# ProPrj_ADC__2025-07-17.net
KiCad netlist of a schematic drawn in EasyEDA Pro
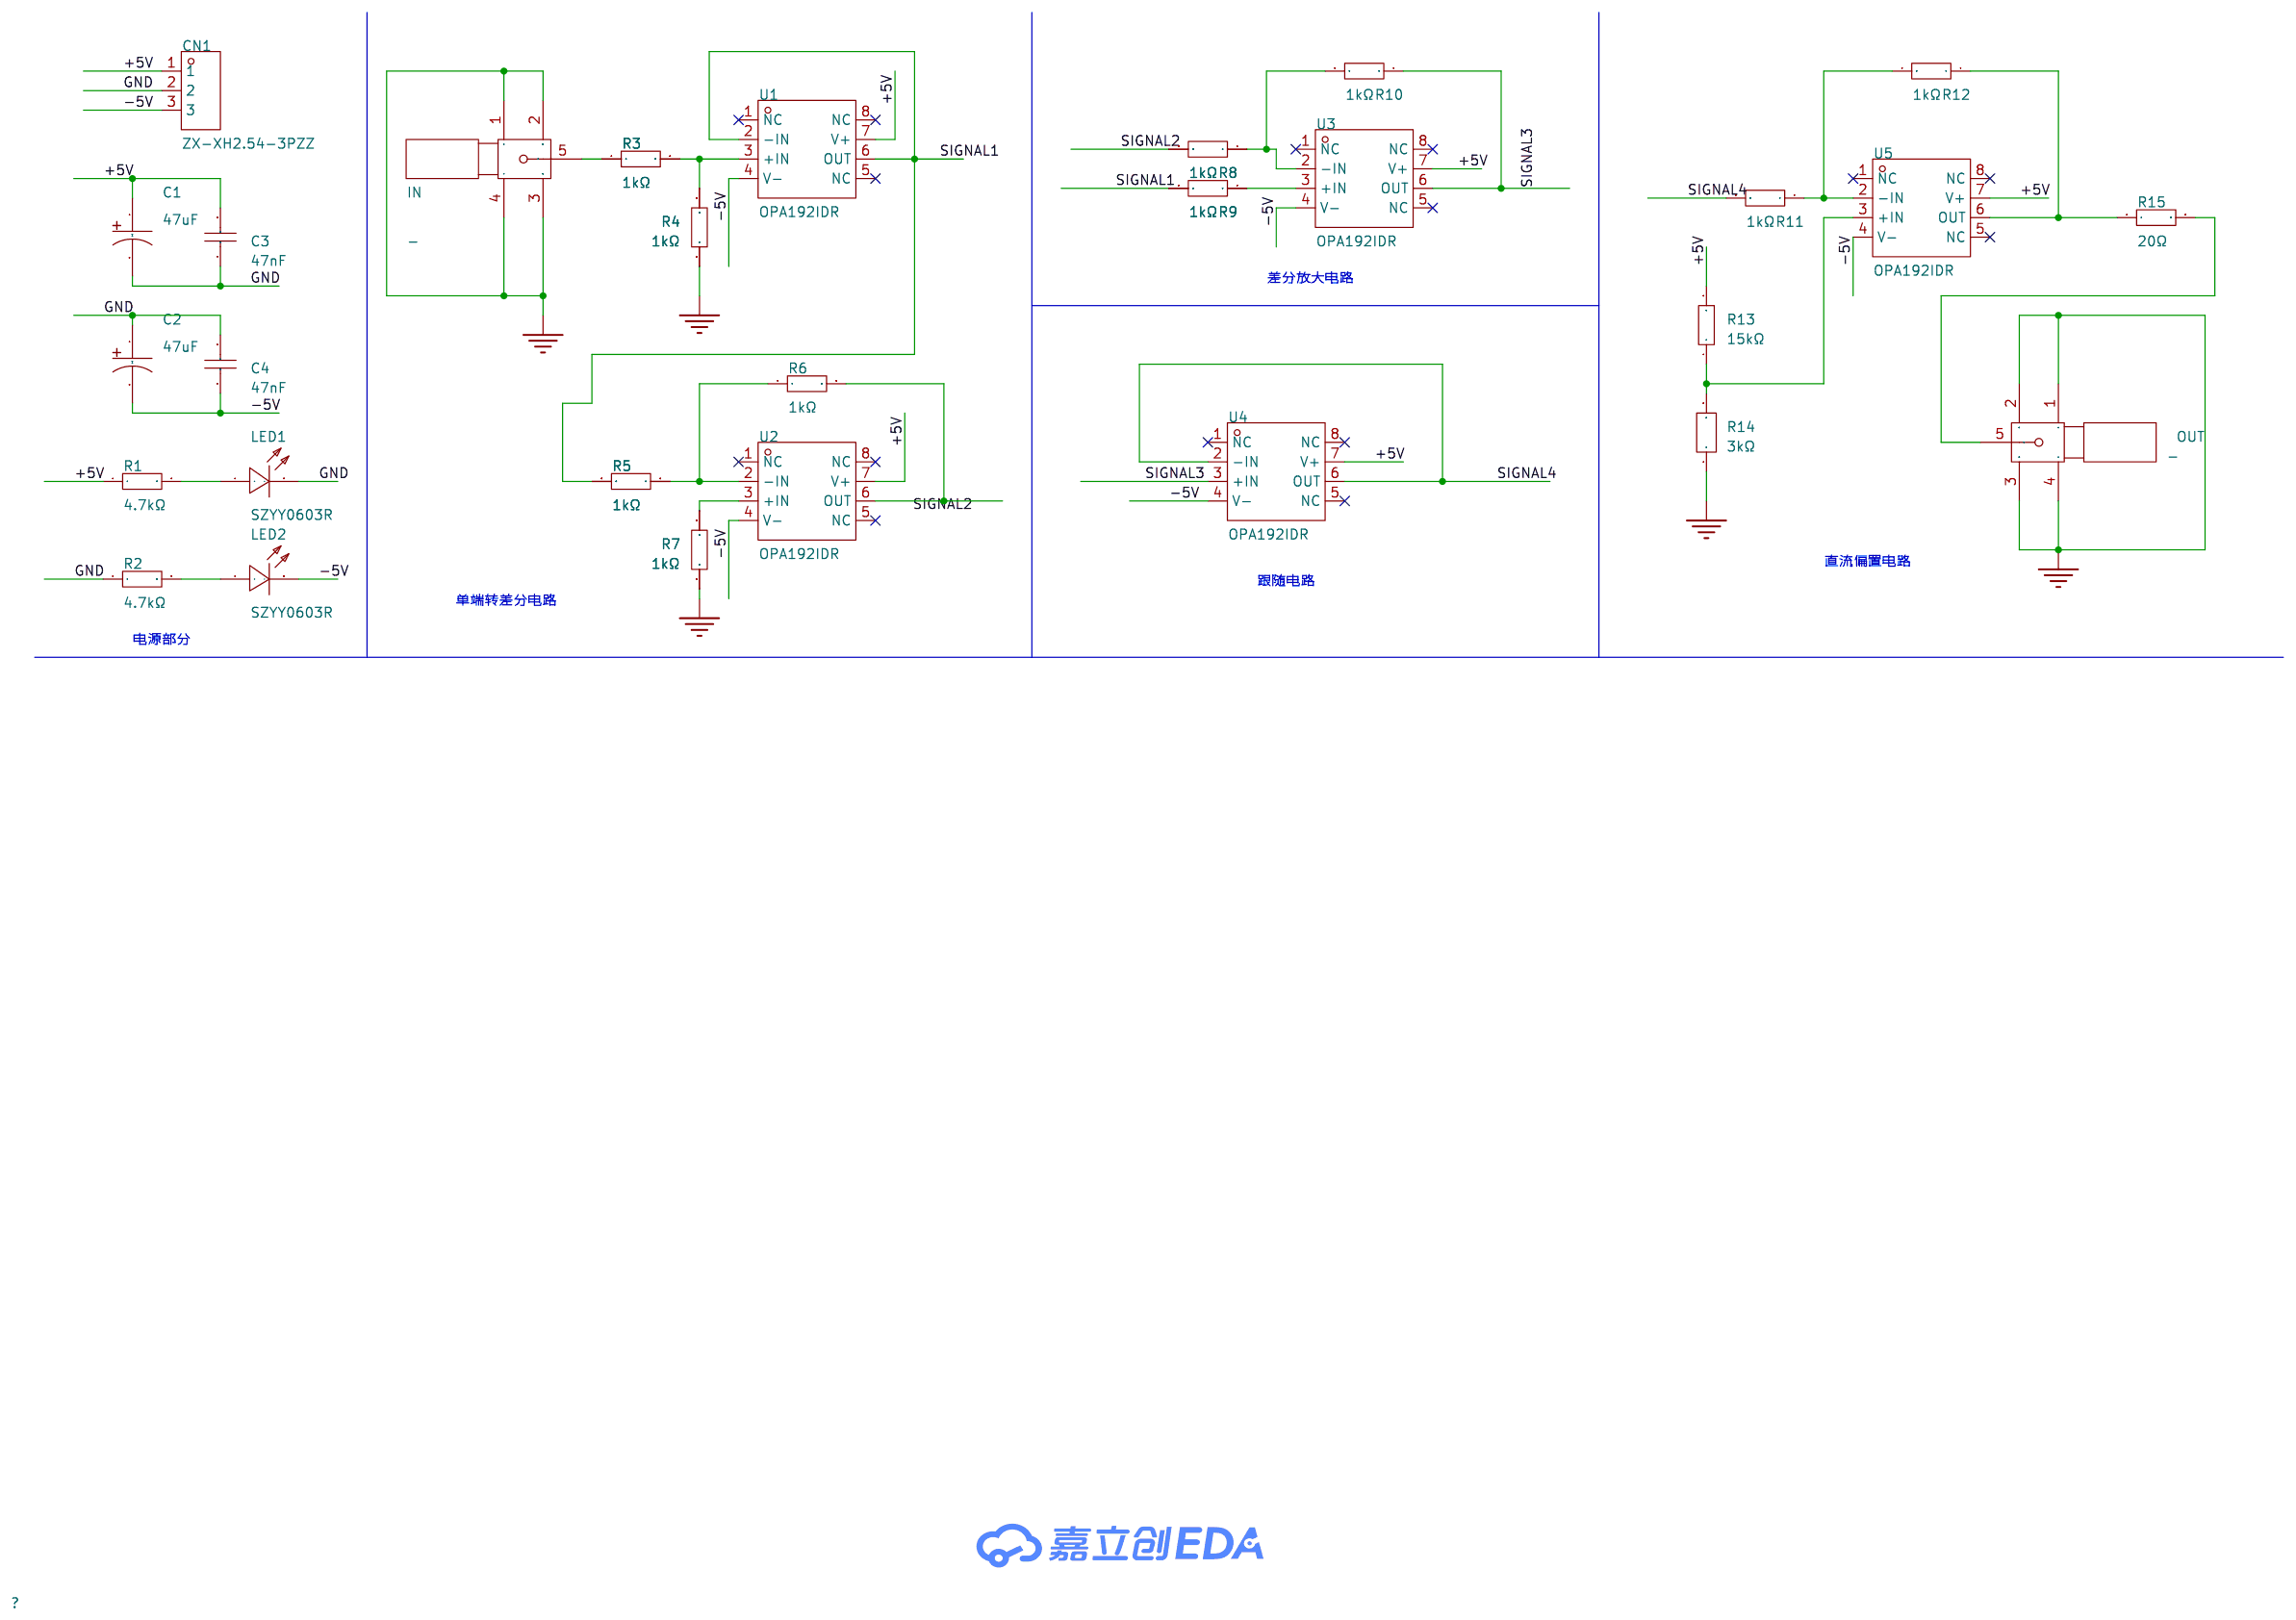
[diagram p0: schematic sheet]

(export (version "E")
  (design (tool "Eeschema 10.0.6"))
  (components
    (comp (ref "C1")
      (value "47uF")
      (footprint "easyedapro:CAP-TH_BD5.0-P2.00-D0.8-FD")
      (description "容值:47uF;精度:±20%;额定电压:25V;纹波电流:250mA@100kHz;等效串联电阻(ESR):300mΩ@100kHz;")
      (fields
        (field (name "Manufacturer Part") "NXB25V47M5*11 2.5TP")
        (field (name "Manufacturer") "SAMYOUNG(韩国三莹)")
      )
      (libsource (lib "easyedapro") (part "NXB25VB47M5*11_2.5TP"))
    )
    (comp (ref "C2")
      (value "47uF")
      (footprint "easyedapro:CAP-TH_BD5.0-P2.00-D0.8-FD")
      (description "容值:47uF;精度:±20%;额定电压:25V;纹波电流:250mA@100kHz;等效串联电阻(ESR):300mΩ@100kHz;")
      (fields
        (field (name "Manufacturer Part") "NXB25V47M5*11 2.5TP")
        (field (name "Manufacturer") "SAMYOUNG(韩国三莹)")
      )
      (libsource (lib "easyedapro") (part "NXB25VB47M5*11_2.5TP"))
    )
    (comp (ref "C3")
      (value "47nF")
      (footprint "easyedapro:C0805")
      (description "容值:47nF;精度:±10%;额定电压:50V;材质(温度系数):X7R;")
      (fields
        (field (name "Manufacturer Part") "CL21B473KBCNNNC")
        (field (name "Manufacturer") "SAMSUNG(三星)")
      )
      (libsource (lib "easyedapro") (part "CL21B473KBCNNNC"))
    )
    (comp (ref "C4")
      (value "47nF")
      (footprint "easyedapro:C0805")
      (description "容值:47nF;精度:±10%;额定电压:50V;材质(温度系数):X7R;")
      (fields
        (field (name "Manufacturer Part") "CL21B473KBCNNNC")
        (field (name "Manufacturer") "SAMSUNG(三星)")
      )
      (libsource (lib "easyedapro") (part "CL21B473KBCNNNC"))
    )
    (comp (ref "CN1")
      (value "ZX-XH2.54-3PZZ")
      (footprint "easyedapro:CONN-TH_3P-P2.54_2501S-3P")
      (fields (field (name "Manufacturer") "Megastar(兆星)"))
      (libsource (lib "easyedapro") (part "ZX-XH2.54-3PZZ"))
    )
    (comp (ref "IN")
      (value "-")
      (footprint "easyedapro:SMA-SMD_BWSMA-KE-P001")
      (description "连接器类型:板端;接口类型:内孔;端口数量:1;接口直径:5.2mm;接口长度/高度:-;频率:-;射频系列:SMA;阻抗:50Ω;样式:偏脚;工作温度:-;")
      (fields
        (field (name "Manufacturer Part") "BWSMA-KE-P001")
        (field (name "Manufacturer") "BAT WIRELESS(蝙蝠无线)")
      )
      (libsource (lib "easyedapro") (part "BWSMA-KE-P001"))
    )
    (comp (ref "LED1")
      (value "SZYY0603R")
      (footprint "easyedapro:LED0603-R-RD")
      (fields (field (name "Manufacturer") "yongyu(永裕光电)"))
      (libsource (lib "easyedapro") (part "SZYY0603R"))
    )
    (comp (ref "LED2")
      (value "SZYY0603R")
      (footprint "easyedapro:LED0603-R-RD")
      (fields (field (name "Manufacturer") "yongyu(永裕光电)"))
      (libsource (lib "easyedapro") (part "SZYY0603R"))
    )
    (comp (ref "OUT")
      (value "-")
      (footprint "easyedapro:SMA-SMD_BWSMA-KE-P001")
      (description "连接器类型:板端;接口类型:内孔;端口数量:1;接口直径:5.2mm;接口长度/高度:-;频率:-;射频系列:SMA;阻抗:50Ω;样式:偏脚;工作温度:-;")
      (fields
        (field (name "Manufacturer Part") "BWSMA-KE-P001")
        (field (name "Manufacturer") "BAT WIRELESS(蝙蝠无线)")
      )
      (libsource (lib "easyedapro") (part "BWSMA-KE-P001"))
    )
    (comp (ref "R1")
      (value "4.7kΩ")
      (footprint "easyedapro:R0805")
      (description "电阻类型:厚膜电阻;阻值:4.7kΩ;精度:±1%;功率:125mW;最大工作电压:150V;温度系数:±100ppm/°C;")
      (fields
        (field (name "Manufacturer Part") "0805W8F4701T5E")
        (field (name "Manufacturer") "UNI-ROYAL(厚声)")
      )
      (libsource (lib "easyedapro") (part "0805W8F4701T5E"))
    )
    (comp (ref "R2")
      (value "4.7kΩ")
      (footprint "easyedapro:R0805")
      (description "电阻类型:厚膜电阻;阻值:4.7kΩ;精度:±1%;功率:125mW;最大工作电压:150V;温度系数:±100ppm/°C;")
      (fields
        (field (name "Manufacturer Part") "0805W8F4701T5E")
        (field (name "Manufacturer") "UNI-ROYAL(厚声)")
      )
      (libsource (lib "easyedapro") (part "0805W8F4701T5E"))
    )
    (comp (ref "R3")
      (value "1kΩ")
      (footprint "easyedapro:R0805")
      (description "电阻类型:厚膜电阻;阻值:1kΩ;精度:±1%;功率:125mW;最大工作电压:150V;温度系数:±100ppm/°C;")
      (fields
        (field (name "Manufacturer Part") "0805W8F1001T5E")
        (field (name "Manufacturer") "UNI-ROYAL(厚声)")
      )
      (libsource (lib "easyedapro") (part "0805W8F1001T5E"))
    )
    (comp (ref "R4")
      (value "1kΩ")
      (footprint "easyedapro:R0805")
      (description "电阻类型:厚膜电阻;阻值:1kΩ;精度:±1%;功率:125mW;最大工作电压:150V;温度系数:±100ppm/°C;")
      (fields
        (field (name "Manufacturer Part") "0805W8F1001T5E")
        (field (name "Manufacturer") "UNI-ROYAL(厚声)")
      )
      (libsource (lib "easyedapro") (part "0805W8F1001T5E"))
    )
    (comp (ref "R5")
      (value "1kΩ")
      (footprint "easyedapro:R0805")
      (description "电阻类型:厚膜电阻;阻值:1kΩ;精度:±1%;功率:125mW;最大工作电压:150V;温度系数:±100ppm/°C;")
      (fields
        (field (name "Manufacturer Part") "0805W8F1001T5E")
        (field (name "Manufacturer") "UNI-ROYAL(厚声)")
      )
      (libsource (lib "easyedapro") (part "0805W8F1001T5E"))
    )
    (comp (ref "R6")
      (value "1kΩ")
      (footprint "easyedapro:R0805")
      (description "电阻类型:厚膜电阻;阻值:1kΩ;精度:±1%;功率:125mW;最大工作电压:150V;温度系数:±100ppm/°C;")
      (fields
        (field (name "Manufacturer Part") "0805W8F1001T5E")
        (field (name "Manufacturer") "UNI-ROYAL(厚声)")
      )
      (libsource (lib "easyedapro") (part "0805W8F1001T5E"))
    )
    (comp (ref "R7")
      (value "1kΩ")
      (footprint "easyedapro:R0805")
      (description "电阻类型:厚膜电阻;阻值:1kΩ;精度:±1%;功率:125mW;最大工作电压:150V;温度系数:±100ppm/°C;")
      (fields
        (field (name "Manufacturer Part") "0805W8F1001T5E")
        (field (name "Manufacturer") "UNI-ROYAL(厚声)")
      )
      (libsource (lib "easyedapro") (part "0805W8F1001T5E"))
    )
    (comp (ref "R8")
      (value "1kΩ")
      (footprint "easyedapro:R0805")
      (description "电阻类型:厚膜电阻;阻值:1kΩ;精度:±1%;功率:125mW;最大工作电压:150V;温度系数:±100ppm/°C;")
      (fields
        (field (name "Manufacturer Part") "0805W8F1001T5E")
        (field (name "Manufacturer") "UNI-ROYAL(厚声)")
      )
      (libsource (lib "easyedapro") (part "0805W8F1001T5E"))
    )
    (comp (ref "R9")
      (value "1kΩ")
      (footprint "easyedapro:R0805")
      (description "电阻类型:厚膜电阻;阻值:1kΩ;精度:±1%;功率:125mW;最大工作电压:150V;温度系数:±100ppm/°C;")
      (fields
        (field (name "Manufacturer Part") "0805W8F1001T5E")
        (field (name "Manufacturer") "UNI-ROYAL(厚声)")
      )
      (libsource (lib "easyedapro") (part "0805W8F1001T5E"))
    )
    (comp (ref "R10")
      (value "1kΩ")
      (footprint "easyedapro:R0805")
      (description "电阻类型:厚膜电阻;阻值:1kΩ;精度:±1%;功率:125mW;最大工作电压:150V;温度系数:±100ppm/°C;")
      (fields
        (field (name "Manufacturer Part") "0805W8F1001T5E")
        (field (name "Manufacturer") "UNI-ROYAL(厚声)")
      )
      (libsource (lib "easyedapro") (part "0805W8F1001T5E"))
    )
    (comp (ref "R11")
      (value "1kΩ")
      (footprint "easyedapro:R0805")
      (description "电阻类型:厚膜电阻;阻值:1kΩ;精度:±1%;功率:125mW;最大工作电压:150V;温度系数:±100ppm/°C;")
      (fields
        (field (name "Manufacturer Part") "0805W8F1001T5E")
        (field (name "Manufacturer") "UNI-ROYAL(厚声)")
      )
      (libsource (lib "easyedapro") (part "0805W8F1001T5E"))
    )
    (comp (ref "R12")
      (value "1kΩ")
      (footprint "easyedapro:R0805")
      (description "电阻类型:厚膜电阻;阻值:1kΩ;精度:±1%;功率:125mW;最大工作电压:150V;温度系数:±100ppm/°C;")
      (fields
        (field (name "Manufacturer Part") "0805W8F1001T5E")
        (field (name "Manufacturer") "UNI-ROYAL(厚声)")
      )
      (libsource (lib "easyedapro") (part "0805W8F1001T5E"))
    )
    (comp (ref "R13")
      (value "15kΩ")
      (footprint "easyedapro:R0805")
      (description "电阻类型:厚膜电阻;阻值:15kΩ;精度:±1%;功率:125mW;最大工作电压:150V;温度系数:±100ppm/°C;")
      (fields
        (field (name "Manufacturer Part") "0805W8F1502T5E")
        (field (name "Manufacturer") "UNI-ROYAL(厚声)")
      )
      (libsource (lib "easyedapro") (part "0805W8F1502T5E"))
    )
    (comp (ref "R14")
      (value "3kΩ")
      (footprint "easyedapro:R0805")
      (description "电阻类型:厚膜电阻;阻值:3kΩ;精度:±5%;功率:125mW;最大工作电压:150V;温度系数:±100ppm/°C;")
      (fields (field (name "Manufacturer Part") "FRC0805J302 TS") (field (name "Manufacturer") "FOJAN(富捷)"))
      (libsource (lib "easyedapro") (part "FRC0805J302 TS"))
    )
    (comp (ref "R15")
      (value "20Ω")
      (footprint "easyedapro:R0805")
      (description "电阻类型:厚膜电阻;阻值:20Ω;精度:±1%;功率:125mW;最大工作电压:150V;温度系数:±200ppm/°C;")
      (fields
        (field (name "Manufacturer Part") "0805W8F200JT5E")
        (field (name "Manufacturer") "UNI-ROYAL(厚声)")
      )
      (libsource (lib "easyedapro") (part "0805W8F200JT5E"))
    )
    (comp (ref "U1")
      (value "OPA192IDR")
      (footprint "easyedapro:SOIC-8_L4.9-W3.9-P1.27-LS6.0-BL")
      (description "放大器数:单路;增益带宽积(GBP):10MHz;输入偏置电流(Ib):5pA;输入失调电压(Vos):5uV;压摆率(SR):20V/us;轨到轨:轨到轨输入,轨到轨输出;")
      (fields (field (name "Manufacturer") "TI(德州仪器)"))
      (libsource (lib "easyedapro") (part "OPA192IDR"))
    )
    (comp (ref "U2")
      (value "OPA192IDR")
      (footprint "easyedapro:SOIC-8_L4.9-W3.9-P1.27-LS6.0-BL")
      (description "放大器数:单路;增益带宽积(GBP):10MHz;输入偏置电流(Ib):5pA;输入失调电压(Vos):5uV;压摆率(SR):20V/us;轨到轨:轨到轨输入,轨到轨输出;")
      (fields (field (name "Manufacturer") "TI(德州仪器)"))
      (libsource (lib "easyedapro") (part "OPA192IDR"))
    )
    (comp (ref "U3")
      (value "OPA192IDR")
      (footprint "easyedapro:SOIC-8_L4.9-W3.9-P1.27-LS6.0-BL")
      (description "放大器数:单路;增益带宽积(GBP):10MHz;输入偏置电流(Ib):5pA;输入失调电压(Vos):5uV;压摆率(SR):20V/us;轨到轨:轨到轨输入,轨到轨输出;")
      (fields (field (name "Manufacturer") "TI(德州仪器)"))
      (libsource (lib "easyedapro") (part "OPA192IDR"))
    )
    (comp (ref "U4")
      (value "OPA192IDR")
      (footprint "easyedapro:SOIC-8_L4.9-W3.9-P1.27-LS6.0-BL")
      (description "放大器数:单路;增益带宽积(GBP):10MHz;输入偏置电流(Ib):5pA;输入失调电压(Vos):5uV;压摆率(SR):20V/us;轨到轨:轨到轨输入,轨到轨输出;")
      (fields (field (name "Manufacturer") "TI(德州仪器)"))
      (libsource (lib "easyedapro") (part "OPA192IDR"))
    )
    (comp (ref "U5")
      (value "OPA192IDR")
      (footprint "easyedapro:SOIC-8_L4.9-W3.9-P1.27-LS6.0-BL")
      (description "放大器数:单路;增益带宽积(GBP):10MHz;输入偏置电流(Ib):5pA;输入失调电压(Vos):5uV;压摆率(SR):20V/us;轨到轨:轨到轨输入,轨到轨输出;")
      (fields (field (name "Manufacturer") "TI(德州仪器)"))
      (libsource (lib "easyedapro") (part "OPA192IDR"))
    )
  )
  (nets
    (net (code "1") (name "/+5V") (class "Default")
      (node (ref "C1") (pin "1") (pinfunction "1_1") (pintype "unspecified"))
      (node (ref "C3") (pin "2") (pinfunction "2_2") (pintype "input"))
      (node (ref "CN1") (pin "1") (pinfunction "1_1") (pintype "unspecified"))
      (node (ref "R1") (pin "1") (pinfunction "1_1") (pintype "input"))
      (node (ref "R13") (pin "2") (pinfunction "2_2") (pintype "input"))
      (node (ref "U1") (pin "7") (pinfunction "V+_7") (pintype "unspecified"))
      (node (ref "U2") (pin "7") (pinfunction "V+_7") (pintype "unspecified"))
      (node (ref "U3") (pin "7") (pinfunction "V+_7") (pintype "unspecified"))
      (node (ref "U4") (pin "7") (pinfunction "V+_7") (pintype "unspecified"))
      (node (ref "U5") (pin "7") (pinfunction "V+_7") (pintype "unspecified"))
    )
    (net (code "2") (name "/-5V") (class "Default")
      (node (ref "C2") (pin "2") (pinfunction "2_2") (pintype "unspecified"))
      (node (ref "C4") (pin "1") (pinfunction "1_1") (pintype "input"))
      (node (ref "CN1") (pin "3") (pinfunction "3_3") (pintype "unspecified"))
      (node (ref "LED2") (pin "2") (pinfunction "-_2") (pintype "unspecified"))
      (node (ref "U1") (pin "4") (pinfunction "V-_4") (pintype "unspecified"))
      (node (ref "U2") (pin "4") (pinfunction "V-_4") (pintype "unspecified"))
      (node (ref "U3") (pin "4") (pinfunction "V-_4") (pintype "unspecified"))
      (node (ref "U4") (pin "4") (pinfunction "V-_4") (pintype "unspecified"))
      (node (ref "U5") (pin "4") (pinfunction "V-_4") (pintype "unspecified"))
    )
    (net (code "3") (name "/SIGNAL1") (class "Default")
      (node (ref "R5") (pin "2") (pinfunction "2_2") (pintype "input"))
      (node (ref "R9") (pin "2") (pinfunction "2_2") (pintype "input"))
      (node (ref "U1") (pin "2") (pinfunction "-IN_2") (pintype "unspecified"))
      (node (ref "U1") (pin "6") (pinfunction "OUT_6") (pintype "unspecified"))
    )
    (net (code "4") (name "/SIGNAL2") (class "Default")
      (node (ref "R6") (pin "2") (pinfunction "2_2") (pintype "input"))
      (node (ref "R8") (pin "2") (pinfunction "2_2") (pintype "input"))
      (node (ref "U2") (pin "6") (pinfunction "OUT_6") (pintype "unspecified"))
    )
    (net (code "5") (name "/SIGNAL3") (class "Default")
      (node (ref "R10") (pin "1") (pinfunction "1_1") (pintype "input"))
      (node (ref "U3") (pin "6") (pinfunction "OUT_6") (pintype "unspecified"))
      (node (ref "U4") (pin "3") (pinfunction "+IN_3") (pintype "unspecified"))
    )
    (net (code "6") (name "/SIGNAL4") (class "Default")
      (node (ref "R11") (pin "2") (pinfunction "2_2") (pintype "input"))
      (node (ref "U4") (pin "2") (pinfunction "-IN_2") (pintype "unspecified"))
      (node (ref "U4") (pin "6") (pinfunction "OUT_6") (pintype "unspecified"))
    )
    (net (code "7") (name "GND") (class "Default")
      (node (ref "C1") (pin "2") (pinfunction "2_2") (pintype "unspecified"))
      (node (ref "C2") (pin "1") (pinfunction "1_1") (pintype "unspecified"))
      (node (ref "C3") (pin "1") (pinfunction "1_1") (pintype "input"))
      (node (ref "C4") (pin "2") (pinfunction "2_2") (pintype "input"))
      (node (ref "CN1") (pin "2") (pinfunction "2_2") (pintype "unspecified"))
      (node (ref "IN") (pin "1") (pinfunction "1_1") (pintype "unspecified"))
      (node (ref "IN") (pin "2") (pinfunction "2_2") (pintype "unspecified"))
      (node (ref "IN") (pin "3") (pinfunction "3_3") (pintype "unspecified"))
      (node (ref "IN") (pin "4") (pinfunction "4_4") (pintype "unspecified"))
      (node (ref "LED1") (pin "2") (pinfunction "-_2") (pintype "unspecified"))
      (node (ref "OUT") (pin "1") (pinfunction "1_1") (pintype "unspecified"))
      (node (ref "OUT") (pin "2") (pinfunction "2_2") (pintype "unspecified"))
      (node (ref "OUT") (pin "3") (pinfunction "3_3") (pintype "unspecified"))
      (node (ref "OUT") (pin "4") (pinfunction "4_4") (pintype "unspecified"))
      (node (ref "R14") (pin "1") (pinfunction "1_1") (pintype "unspecified"))
      (node (ref "R2") (pin "1") (pinfunction "1_1") (pintype "input"))
      (node (ref "R4") (pin "1") (pinfunction "1_1") (pintype "input"))
      (node (ref "R7") (pin "1") (pinfunction "1_1") (pintype "input"))
    )
    (net (code "8") (name "Net-(IN-Pad5)") (class "Default")
      (node (ref "IN") (pin "5") (pinfunction "5_5") (pintype "unspecified"))
      (node (ref "R3") (pin "1") (pinfunction "1_1") (pintype "input"))
    )
    (net (code "9") (name "Net-(LED1-+)") (class "Default")
      (node (ref "LED1") (pin "1") (pinfunction "+_1") (pintype "unspecified"))
      (node (ref "R1") (pin "2") (pinfunction "2_2") (pintype "input"))
    )
    (net (code "10") (name "Net-(LED2-+)") (class "Default")
      (node (ref "LED2") (pin "1") (pinfunction "+_1") (pintype "unspecified"))
      (node (ref "R2") (pin "2") (pinfunction "2_2") (pintype "input"))
    )
    (net (code "11") (name "Net-(OUT-Pad5)") (class "Default")
      (node (ref "OUT") (pin "5") (pinfunction "5_5") (pintype "unspecified"))
      (node (ref "R15") (pin "2") (pinfunction "2_2") (pintype "input"))
    )
    (net (code "12") (name "Net-(U1-+IN)") (class "Default")
      (node (ref "R3") (pin "2") (pinfunction "2_2") (pintype "input"))
      (node (ref "R4") (pin "2") (pinfunction "2_2") (pintype "input"))
      (node (ref "U1") (pin "3") (pinfunction "+IN_3") (pintype "unspecified"))
    )
    (net (code "13") (name "Net-(U2-+IN)") (class "Default")
      (node (ref "R7") (pin "2") (pinfunction "2_2") (pintype "input"))
      (node (ref "U2") (pin "3") (pinfunction "+IN_3") (pintype "unspecified"))
    )
    (net (code "14") (name "Net-(U2--IN)") (class "Default")
      (node (ref "R5") (pin "1") (pinfunction "1_1") (pintype "input"))
      (node (ref "R6") (pin "1") (pinfunction "1_1") (pintype "input"))
      (node (ref "U2") (pin "2") (pinfunction "-IN_2") (pintype "unspecified"))
    )
    (net (code "15") (name "Net-(U3-+IN)") (class "Default")
      (node (ref "R9") (pin "1") (pinfunction "1_1") (pintype "input"))
      (node (ref "U3") (pin "3") (pinfunction "+IN_3") (pintype "unspecified"))
    )
    (net (code "16") (name "Net-(U3--IN)") (class "Default")
      (node (ref "R10") (pin "2") (pinfunction "2_2") (pintype "input"))
      (node (ref "R8") (pin "1") (pinfunction "1_1") (pintype "input"))
      (node (ref "U3") (pin "2") (pinfunction "-IN_2") (pintype "unspecified"))
    )
    (net (code "17") (name "Net-(U5-+IN)") (class "Default")
      (node (ref "R13") (pin "1") (pinfunction "1_1") (pintype "input"))
      (node (ref "R14") (pin "2") (pinfunction "2_2") (pintype "unspecified"))
      (node (ref "U5") (pin "3") (pinfunction "+IN_3") (pintype "unspecified"))
    )
    (net (code "18") (name "Net-(U5--IN)") (class "Default")
      (node (ref "R11") (pin "1") (pinfunction "1_1") (pintype "input"))
      (node (ref "R12") (pin "2") (pinfunction "2_2") (pintype "input"))
      (node (ref "U5") (pin "2") (pinfunction "-IN_2") (pintype "unspecified"))
    )
    (net (code "19") (name "Net-(U5-OUT)") (class "Default")
      (node (ref "R12") (pin "1") (pinfunction "1_1") (pintype "input"))
      (node (ref "R15") (pin "1") (pinfunction "1_1") (pintype "input"))
      (node (ref "U5") (pin "6") (pinfunction "OUT_6") (pintype "unspecified"))
    )
    (net (code "20") (name "unconnected-(U1-NC-Pad1)") (class "Default")
      (node (ref "U1") (pin "1") (pinfunction "NC_1") (pintype "unspecified+no_connect"))
    )
    (net (code "21") (name "unconnected-(U1-NC-Pad5)") (class "Default")
      (node (ref "U1") (pin "5") (pinfunction "NC_5") (pintype "unspecified+no_connect"))
    )
    (net (code "22") (name "unconnected-(U1-NC-Pad8)") (class "Default")
      (node (ref "U1") (pin "8") (pinfunction "NC_8") (pintype "unspecified+no_connect"))
    )
    (net (code "23") (name "unconnected-(U2-NC-Pad1)") (class "Default")
      (node (ref "U2") (pin "1") (pinfunction "NC_1") (pintype "unspecified+no_connect"))
    )
    (net (code "24") (name "unconnected-(U2-NC-Pad5)") (class "Default")
      (node (ref "U2") (pin "5") (pinfunction "NC_5") (pintype "unspecified+no_connect"))
    )
    (net (code "25") (name "unconnected-(U2-NC-Pad8)") (class "Default")
      (node (ref "U2") (pin "8") (pinfunction "NC_8") (pintype "unspecified+no_connect"))
    )
    (net (code "26") (name "unconnected-(U3-NC-Pad1)") (class "Default")
      (node (ref "U3") (pin "1") (pinfunction "NC_1") (pintype "unspecified+no_connect"))
    )
    (net (code "27") (name "unconnected-(U3-NC-Pad5)") (class "Default")
      (node (ref "U3") (pin "5") (pinfunction "NC_5") (pintype "unspecified+no_connect"))
    )
    (net (code "28") (name "unconnected-(U3-NC-Pad8)") (class "Default")
      (node (ref "U3") (pin "8") (pinfunction "NC_8") (pintype "unspecified+no_connect"))
    )
    (net (code "29") (name "unconnected-(U4-NC-Pad1)") (class "Default")
      (node (ref "U4") (pin "1") (pinfunction "NC_1") (pintype "unspecified+no_connect"))
    )
    (net (code "30") (name "unconnected-(U4-NC-Pad5)") (class "Default")
      (node (ref "U4") (pin "5") (pinfunction "NC_5") (pintype "unspecified+no_connect"))
    )
    (net (code "31") (name "unconnected-(U4-NC-Pad8)") (class "Default")
      (node (ref "U4") (pin "8") (pinfunction "NC_8") (pintype "unspecified+no_connect"))
    )
    (net (code "32") (name "unconnected-(U5-NC-Pad1)") (class "Default")
      (node (ref "U5") (pin "1") (pinfunction "NC_1") (pintype "unspecified+no_connect"))
    )
    (net (code "33") (name "unconnected-(U5-NC-Pad5)") (class "Default")
      (node (ref "U5") (pin "5") (pinfunction "NC_5") (pintype "unspecified+no_connect"))
    )
    (net (code "34") (name "unconnected-(U5-NC-Pad8)") (class "Default")
      (node (ref "U5") (pin "8") (pinfunction "NC_8") (pintype "unspecified+no_connect"))
    )
  )
)
